# OptronV7_PCB.net
KiCad netlist of a schematic drawn in EAGLE
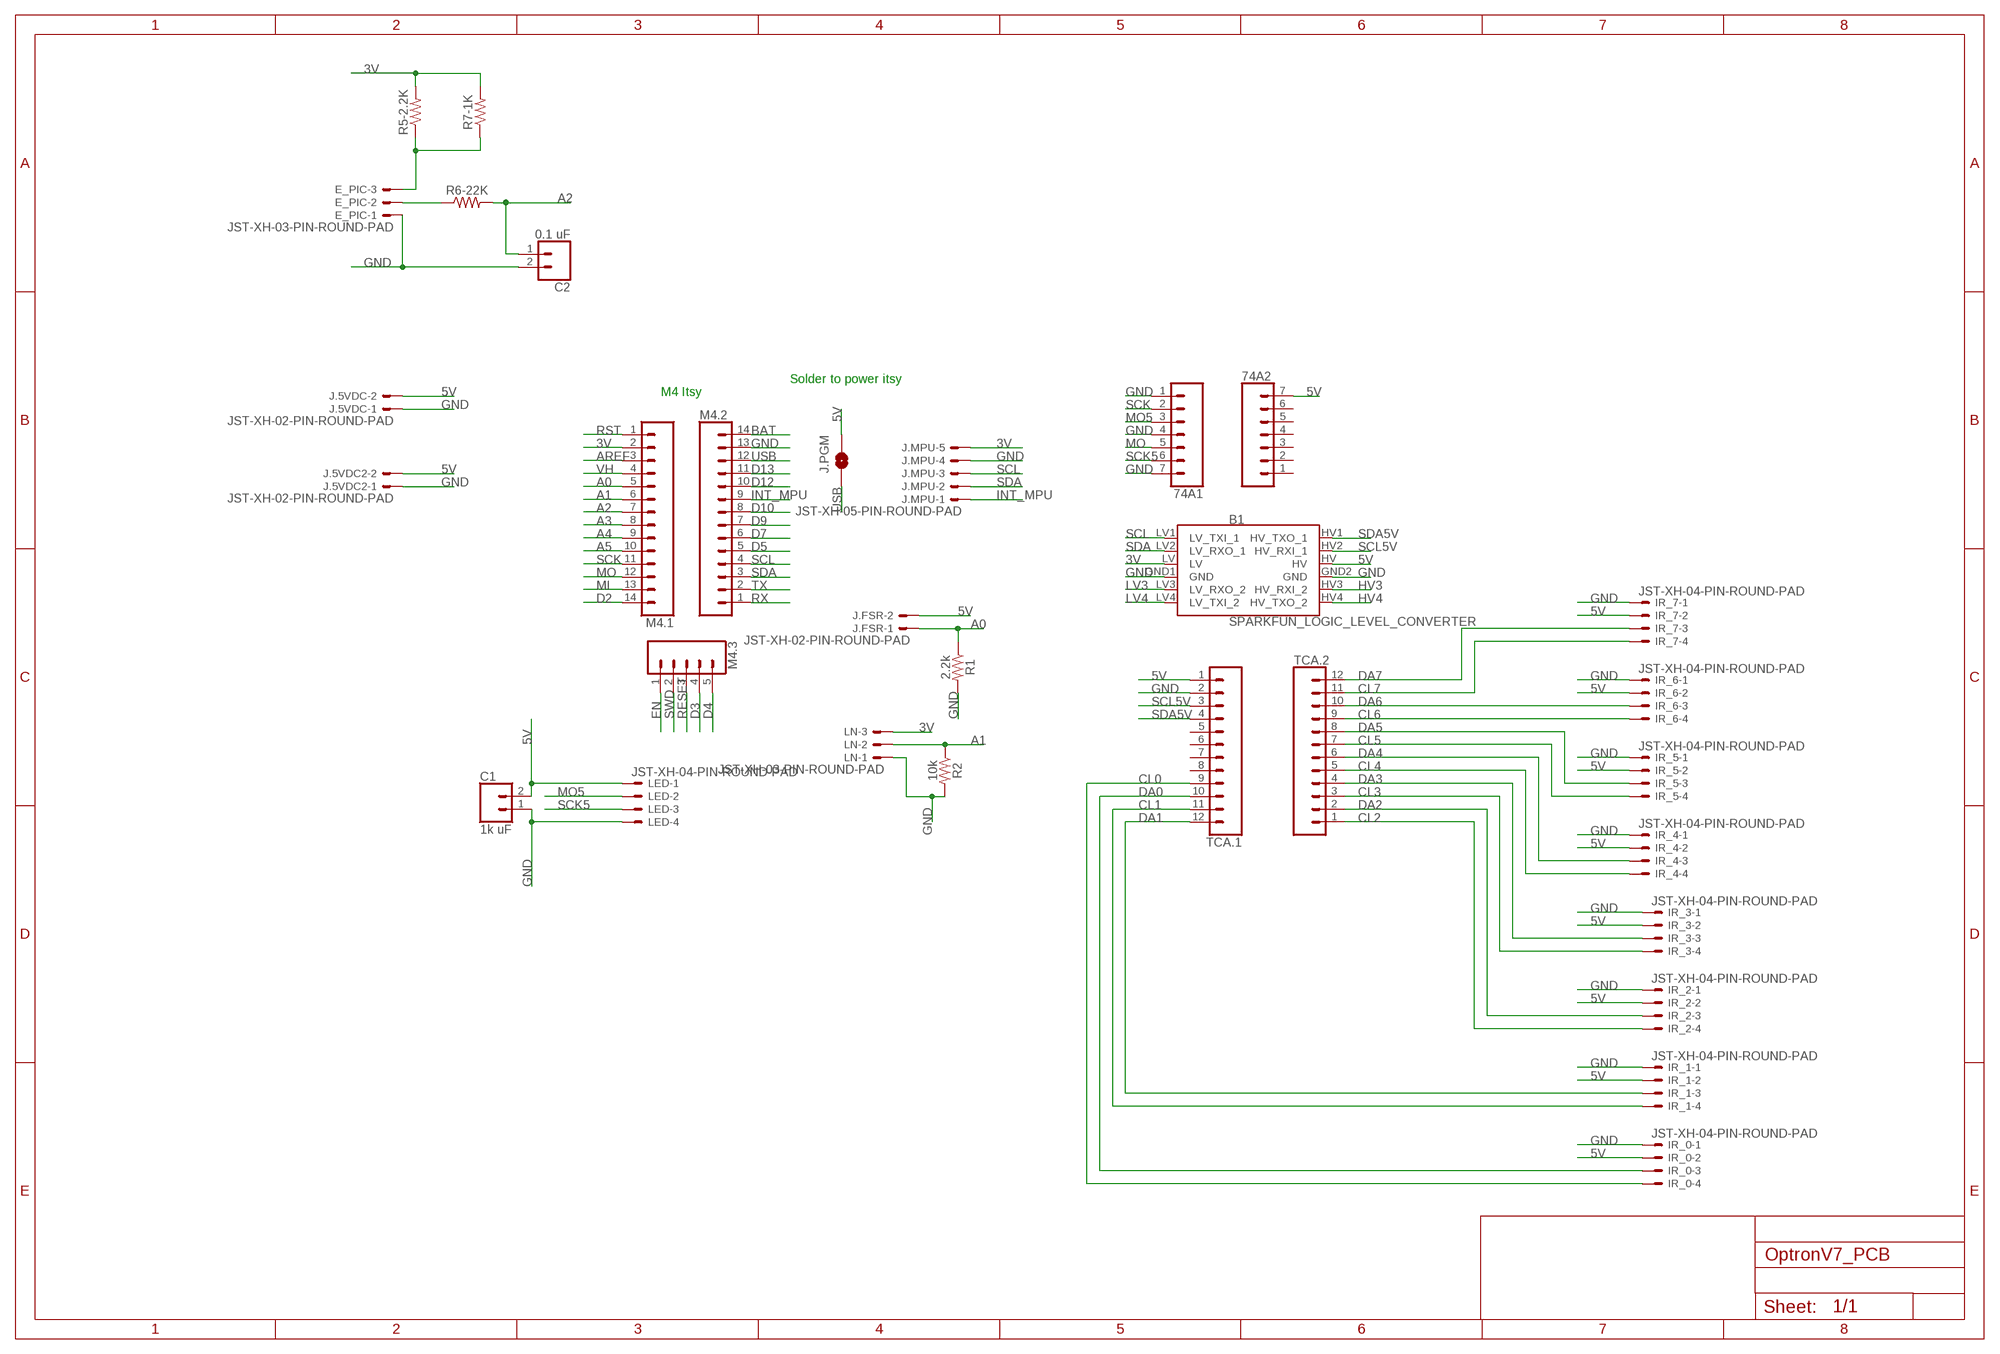
[diagram p0: schematic, sheet 1]

(export (version "E")
  (design (tool "Eeschema 10.0.6"))
  (components
    (comp (ref "74A1")
      (value "CONN_07")
      (footprint "eagle-import:1X07")
      (libsource (lib "eagle-import") (part "CONN_07"))
    )
    (comp (ref "74A2")
      (value "CONN_07")
      (footprint "eagle-import:1X07")
      (libsource (lib "eagle-import") (part "CONN_07"))
    )
    (comp (ref "B1")
      (value "SPARKFUN_LOGIC_LEVEL_CONVERTER")
      (footprint "eagle-import:SPARKFUN_LOGIC_LEVEL_CONVERTER")
      (libsource (lib "eagle-import") (part "SPARKFUN_LOGIC_LEVEL_CONVERTER"))
    )
    (comp (ref "C1")
      (value "1k uF")
      (footprint "eagle-import:1X02")
      (libsource (lib "eagle-import") (part "CONN_02"))
    )
    (comp (ref "C2")
      (value "0.1 uF")
      (footprint "eagle-import:1X02")
      (libsource (lib "eagle-import") (part "CONN_02"))
    )
    (comp (ref "E_PIC")
      (value "JST-XH-03-PIN-ROUND-PAD")
      (footprint "eagle-import:JST-XH-03-PACKAGE-ROUND-PAD")
      (libsource (lib "eagle-import") (part "JST-XH-03-PIN-ROUND-PAD"))
    )
    (comp (ref "IR_0")
      (value "JST-XH-04-PIN-ROUND-PAD")
      (footprint "eagle-import:JST-XH-04-PACKAGE-ROUND-PAD")
      (libsource (lib "eagle-import") (part "JST-XH-04-PIN-ROUND-PAD"))
    )
    (comp (ref "IR_1")
      (value "JST-XH-04-PIN-ROUND-PAD")
      (footprint "eagle-import:JST-XH-04-PACKAGE-ROUND-PAD")
      (libsource (lib "eagle-import") (part "JST-XH-04-PIN-ROUND-PAD"))
    )
    (comp (ref "IR_2")
      (value "JST-XH-04-PIN-ROUND-PAD")
      (footprint "eagle-import:JST-XH-04-PACKAGE-ROUND-PAD")
      (libsource (lib "eagle-import") (part "JST-XH-04-PIN-ROUND-PAD"))
    )
    (comp (ref "IR_3")
      (value "JST-XH-04-PIN-ROUND-PAD")
      (footprint "eagle-import:JST-XH-04-PACKAGE-ROUND-PAD")
      (libsource (lib "eagle-import") (part "JST-XH-04-PIN-ROUND-PAD"))
    )
    (comp (ref "IR_4")
      (value "JST-XH-04-PIN-ROUND-PAD")
      (footprint "eagle-import:JST-XH-04-PACKAGE-ROUND-PAD")
      (libsource (lib "eagle-import") (part "JST-XH-04-PIN-ROUND-PAD"))
    )
    (comp (ref "IR_5")
      (value "JST-XH-04-PIN-ROUND-PAD")
      (footprint "eagle-import:JST-XH-04-PACKAGE-ROUND-PAD")
      (libsource (lib "eagle-import") (part "JST-XH-04-PIN-ROUND-PAD"))
    )
    (comp (ref "IR_6")
      (value "JST-XH-04-PIN-ROUND-PAD")
      (footprint "eagle-import:JST-XH-04-PACKAGE-ROUND-PAD")
      (libsource (lib "eagle-import") (part "JST-XH-04-PIN-ROUND-PAD"))
    )
    (comp (ref "IR_7")
      (value "JST-XH-04-PIN-ROUND-PAD")
      (footprint "eagle-import:JST-XH-04-PACKAGE-ROUND-PAD")
      (libsource (lib "eagle-import") (part "JST-XH-04-PIN-ROUND-PAD"))
    )
    (comp (ref "J.5VDC")
      (value "JST-XH-02-PIN-ROUND-PAD")
      (footprint "eagle-import:JST-XH-02-PACKAGE-ROUND-PAD")
      (libsource (lib "eagle-import") (part "JST-XH-02-PIN-ROUND-PAD"))
    )
    (comp (ref "J.5VDC2")
      (value "JST-XH-02-PIN-ROUND-PAD")
      (footprint "eagle-import:JST-XH-02-PACKAGE-ROUND-PAD")
      (libsource (lib "eagle-import") (part "JST-XH-02-PIN-ROUND-PAD"))
    )
    (comp (ref "J.FSR")
      (value "JST-XH-02-PIN-ROUND-PAD")
      (footprint "eagle-import:JST-XH-02-PACKAGE-ROUND-PAD")
      (libsource (lib "eagle-import") (part "JST-XH-02-PIN-ROUND-PAD"))
    )
    (comp (ref "J.MPU")
      (value "JST-XH-05-PIN-ROUND-PAD")
      (footprint "eagle-import:JST-XH-05-PACKAGE-ROUND-PAD")
      (libsource (lib "eagle-import") (part "JST-XH-05-PIN-ROUND-PAD"))
    )
    (comp (ref "J.PGM")
      (value "JUMPER-SMT_2_NO_NO-SILK")
      (footprint "eagle-import:SMT-JUMPER_2_NO_NO-SILK")
      (libsource (lib "eagle-import") (part "JUMPER-SMT_2_NO_NO-SILK"))
    )
    (comp (ref "LED")
      (value "JST-XH-04-PIN-ROUND-PAD")
      (footprint "eagle-import:JST-XH-04-PACKAGE-ROUND-PAD")
      (libsource (lib "eagle-import") (part "JST-XH-04-PIN-ROUND-PAD"))
    )
    (comp (ref "LN")
      (value "JST-XH-03-PIN-ROUND-PAD")
      (footprint "eagle-import:JST-XH-03-PACKAGE-ROUND-PAD")
      (libsource (lib "eagle-import") (part "JST-XH-03-PIN-ROUND-PAD"))
    )
    (comp (ref "M4.1")
      (value "CONN_14")
      (footprint "eagle-import:1X14")
      (libsource (lib "eagle-import") (part "CONN_14"))
    )
    (comp (ref "M4.2")
      (value "CONN_14")
      (footprint "eagle-import:1X14")
      (libsource (lib "eagle-import") (part "CONN_14"))
    )
    (comp (ref "M4.3")
      (value "CONN_05")
      (footprint "eagle-import:1X05")
      (libsource (lib "eagle-import") (part "CONN_05"))
    )
    (comp (ref "R1")
      (value "2.2k")
      (footprint "eagle-import:AXIAL-0.3")
      (libsource (lib "eagle-import") (part "10KOHM-HORIZ-1/4W-5%"))
    )
    (comp (ref "R2")
      (value "10k")
      (footprint "eagle-import:AXIAL-0.3")
      (libsource (lib "eagle-import") (part "10KOHM-HORIZ-1/4W-5%"))
    )
    (comp (ref "R5-2.2K")
      (value "RESISTORAXIAL-0.3")
      (footprint "eagle-import:AXIAL-0.3")
      (libsource (lib "eagle-import") (part "RESISTORAXIAL-0.3"))
    )
    (comp (ref "R6-22K")
      (value "RESISTORAXIAL-0.3")
      (footprint "eagle-import:AXIAL-0.3")
      (libsource (lib "eagle-import") (part "RESISTORAXIAL-0.3"))
    )
    (comp (ref "R7-1K")
      (value "RESISTORAXIAL-0.3")
      (footprint "eagle-import:AXIAL-0.3")
      (libsource (lib "eagle-import") (part "RESISTORAXIAL-0.3"))
    )
    (comp (ref "TCA.1")
      (value "CONN_12")
      (footprint "eagle-import:1X12")
      (libsource (lib "eagle-import") (part "CONN_12"))
    )
    (comp (ref "TCA.2")
      (value "CONN_12")
      (footprint "eagle-import:1X12")
      (libsource (lib "eagle-import") (part "CONN_12"))
    )
  )
  (nets
    (net (code "1") (name "/3V") (class "Default")
      (node (ref "B1") (pin "LV") (pinfunction "LV_LV") (pintype "power_in"))
      (node (ref "J.MPU") (pin "5") (pinfunction "S_5") (pintype "passive"))
      (node (ref "LN") (pin "3") (pinfunction "S_3") (pintype "passive"))
      (node (ref "M4.1") (pin "2") (pinfunction "2_2") (pintype "passive"))
      (node (ref "R5-2.2K") (pin "P$2") (pinfunction "2_P$2") (pintype "passive"))
      (node (ref "R7-1K") (pin "P$2") (pinfunction "2_P$2") (pintype "passive"))
    )
    (net (code "2") (name "/5V") (class "Default")
      (node (ref "74A2") (pin "7") (pinfunction "7_7") (pintype "passive"))
      (node (ref "B1") (pin "HV") (pinfunction "HV_HV") (pintype "power_in"))
      (node (ref "C1") (pin "2") (pinfunction "2_2") (pintype "passive"))
      (node (ref "IR_0") (pin "2") (pinfunction "S_2") (pintype "passive"))
      (node (ref "IR_1") (pin "2") (pinfunction "S_2") (pintype "passive"))
      (node (ref "IR_2") (pin "2") (pinfunction "S_2") (pintype "passive"))
      (node (ref "IR_3") (pin "2") (pinfunction "S_2") (pintype "passive"))
      (node (ref "IR_4") (pin "2") (pinfunction "S_2") (pintype "passive"))
      (node (ref "IR_5") (pin "2") (pinfunction "S_2") (pintype "passive"))
      (node (ref "IR_6") (pin "2") (pinfunction "S_2") (pintype "passive"))
      (node (ref "IR_7") (pin "2") (pinfunction "S_2") (pintype "passive"))
      (node (ref "J.5VDC") (pin "2") (pinfunction "S_2") (pintype "passive"))
      (node (ref "J.5VDC2") (pin "2") (pinfunction "S_2") (pintype "passive"))
      (node (ref "J.FSR") (pin "2") (pinfunction "S_2") (pintype "passive"))
      (node (ref "J.PGM") (pin "2") (pinfunction "2_2") (pintype "passive"))
      (node (ref "LED") (pin "1") (pinfunction "S_1") (pintype "passive"))
      (node (ref "TCA.1") (pin "1") (pinfunction "1_1") (pintype "passive"))
    )
    (net (code "3") (name "/A0") (class "Default")
      (node (ref "J.FSR") (pin "1") (pinfunction "S_1") (pintype "passive"))
      (node (ref "M4.1") (pin "5") (pinfunction "5_5") (pintype "passive"))
      (node (ref "R1") (pin "P$1") (pinfunction "1_P$1") (pintype "passive"))
    )
    (net (code "4") (name "/A1") (class "Default")
      (node (ref "LN") (pin "2") (pinfunction "S_2") (pintype "passive"))
      (node (ref "M4.1") (pin "6") (pinfunction "6_6") (pintype "passive"))
      (node (ref "R2") (pin "P$1") (pinfunction "1_P$1") (pintype "passive"))
    )
    (net (code "5") (name "/A2") (class "Default")
      (node (ref "C2") (pin "1") (pinfunction "1_1") (pintype "passive"))
      (node (ref "M4.1") (pin "7") (pinfunction "7_7") (pintype "passive"))
      (node (ref "R6-22K") (pin "P$2") (pinfunction "2_P$2") (pintype "passive"))
    )
    (net (code "6") (name "/A3") (class "Default")
      (node (ref "M4.1") (pin "8") (pinfunction "8_8") (pintype "passive"))
    )
    (net (code "7") (name "/A4") (class "Default")
      (node (ref "M4.1") (pin "9") (pinfunction "9_9") (pintype "passive"))
    )
    (net (code "8") (name "/A5") (class "Default")
      (node (ref "M4.1") (pin "10") (pinfunction "10_10") (pintype "passive"))
    )
    (net (code "9") (name "/AREF") (class "Default")
      (node (ref "M4.1") (pin "3") (pinfunction "3_3") (pintype "passive"))
    )
    (net (code "10") (name "/BAT") (class "Default")
      (node (ref "M4.2") (pin "14") (pinfunction "14_14") (pintype "passive"))
    )
    (net (code "11") (name "/CL0") (class "Default")
      (node (ref "IR_0") (pin "4") (pinfunction "S_4") (pintype "passive"))
      (node (ref "TCA.1") (pin "9") (pinfunction "9_9") (pintype "passive"))
    )
    (net (code "12") (name "/CL1") (class "Default")
      (node (ref "IR_1") (pin "4") (pinfunction "S_4") (pintype "passive"))
      (node (ref "TCA.1") (pin "11") (pinfunction "11_11") (pintype "passive"))
    )
    (net (code "13") (name "/CL2") (class "Default")
      (node (ref "IR_2") (pin "4") (pinfunction "S_4") (pintype "passive"))
      (node (ref "TCA.2") (pin "1") (pinfunction "1_1") (pintype "passive"))
    )
    (net (code "14") (name "/CL3") (class "Default")
      (node (ref "IR_3") (pin "4") (pinfunction "S_4") (pintype "passive"))
      (node (ref "TCA.2") (pin "3") (pinfunction "3_3") (pintype "passive"))
    )
    (net (code "15") (name "/CL4") (class "Default")
      (node (ref "IR_4") (pin "4") (pinfunction "S_4") (pintype "passive"))
      (node (ref "TCA.2") (pin "5") (pinfunction "5_5") (pintype "passive"))
    )
    (net (code "16") (name "/CL5") (class "Default")
      (node (ref "IR_5") (pin "4") (pinfunction "S_4") (pintype "passive"))
      (node (ref "TCA.2") (pin "7") (pinfunction "7_7") (pintype "passive"))
    )
    (net (code "17") (name "/CL6") (class "Default")
      (node (ref "IR_6") (pin "4") (pinfunction "S_4") (pintype "passive"))
      (node (ref "TCA.2") (pin "9") (pinfunction "9_9") (pintype "passive"))
    )
    (net (code "18") (name "/CL7") (class "Default")
      (node (ref "IR_7") (pin "4") (pinfunction "S_4") (pintype "passive"))
      (node (ref "TCA.2") (pin "11") (pinfunction "11_11") (pintype "passive"))
    )
    (net (code "19") (name "/D2") (class "Default")
      (node (ref "M4.1") (pin "14") (pinfunction "14_14") (pintype "passive"))
    )
    (net (code "20") (name "/D3") (class "Default")
      (node (ref "M4.3") (pin "4") (pinfunction "4_4") (pintype "passive"))
    )
    (net (code "21") (name "/D4") (class "Default")
      (node (ref "M4.3") (pin "5") (pinfunction "5_5") (pintype "passive"))
    )
    (net (code "22") (name "/D5") (class "Default")
      (node (ref "M4.2") (pin "5") (pinfunction "5_5") (pintype "passive"))
    )
    (net (code "23") (name "/D7") (class "Default")
      (node (ref "M4.2") (pin "6") (pinfunction "6_6") (pintype "passive"))
    )
    (net (code "24") (name "/D9") (class "Default")
      (node (ref "M4.2") (pin "7") (pinfunction "7_7") (pintype "passive"))
    )
    (net (code "25") (name "/D10") (class "Default")
      (node (ref "M4.2") (pin "8") (pinfunction "8_8") (pintype "passive"))
    )
    (net (code "26") (name "/D12") (class "Default")
      (node (ref "M4.2") (pin "10") (pinfunction "10_10") (pintype "passive"))
    )
    (net (code "27") (name "/D13") (class "Default")
      (node (ref "M4.2") (pin "11") (pinfunction "11_11") (pintype "passive"))
    )
    (net (code "28") (name "/DA0") (class "Default")
      (node (ref "IR_0") (pin "3") (pinfunction "S_3") (pintype "passive"))
      (node (ref "TCA.1") (pin "10") (pinfunction "10_10") (pintype "passive"))
    )
    (net (code "29") (name "/DA1") (class "Default")
      (node (ref "IR_1") (pin "3") (pinfunction "S_3") (pintype "passive"))
      (node (ref "TCA.1") (pin "12") (pinfunction "12_12") (pintype "passive"))
    )
    (net (code "30") (name "/DA2") (class "Default")
      (node (ref "IR_2") (pin "3") (pinfunction "S_3") (pintype "passive"))
      (node (ref "TCA.2") (pin "2") (pinfunction "2_2") (pintype "passive"))
    )
    (net (code "31") (name "/DA3") (class "Default")
      (node (ref "IR_3") (pin "3") (pinfunction "S_3") (pintype "passive"))
      (node (ref "TCA.2") (pin "4") (pinfunction "4_4") (pintype "passive"))
    )
    (net (code "32") (name "/DA4") (class "Default")
      (node (ref "IR_4") (pin "3") (pinfunction "S_3") (pintype "passive"))
      (node (ref "TCA.2") (pin "6") (pinfunction "6_6") (pintype "passive"))
    )
    (net (code "33") (name "/DA5") (class "Default")
      (node (ref "IR_5") (pin "3") (pinfunction "S_3") (pintype "passive"))
      (node (ref "TCA.2") (pin "8") (pinfunction "8_8") (pintype "passive"))
    )
    (net (code "34") (name "/DA6") (class "Default")
      (node (ref "IR_6") (pin "3") (pinfunction "S_3") (pintype "passive"))
      (node (ref "TCA.2") (pin "10") (pinfunction "10_10") (pintype "passive"))
    )
    (net (code "35") (name "/DA7") (class "Default")
      (node (ref "IR_7") (pin "3") (pinfunction "S_3") (pintype "passive"))
      (node (ref "TCA.2") (pin "12") (pinfunction "12_12") (pintype "passive"))
    )
    (net (code "36") (name "/EN") (class "Default")
      (node (ref "M4.3") (pin "1") (pinfunction "1_1") (pintype "passive"))
    )
    (net (code "37") (name "/GND") (class "Default")
      (node (ref "74A1") (pin "1") (pinfunction "1_1") (pintype "passive"))
      (node (ref "74A1") (pin "4") (pinfunction "4_4") (pintype "passive"))
      (node (ref "74A1") (pin "7") (pinfunction "7_7") (pintype "passive"))
      (node (ref "B1") (pin "GND1") (pinfunction "GND_GND1") (pintype "power_in"))
      (node (ref "B1") (pin "GND2") (pinfunction "GND_GND2") (pintype "power_in"))
      (node (ref "C1") (pin "1") (pinfunction "1_1") (pintype "passive"))
      (node (ref "C2") (pin "2") (pinfunction "2_2") (pintype "passive"))
      (node (ref "E_PIC") (pin "1") (pinfunction "S_1") (pintype "passive"))
      (node (ref "IR_0") (pin "1") (pinfunction "S_1") (pintype "passive"))
      (node (ref "IR_1") (pin "1") (pinfunction "S_1") (pintype "passive"))
      (node (ref "IR_2") (pin "1") (pinfunction "S_1") (pintype "passive"))
      (node (ref "IR_3") (pin "1") (pinfunction "S_1") (pintype "passive"))
      (node (ref "IR_4") (pin "1") (pinfunction "S_1") (pintype "passive"))
      (node (ref "IR_5") (pin "1") (pinfunction "S_1") (pintype "passive"))
      (node (ref "IR_6") (pin "1") (pinfunction "S_1") (pintype "passive"))
      (node (ref "IR_7") (pin "1") (pinfunction "S_1") (pintype "passive"))
      (node (ref "J.5VDC") (pin "1") (pinfunction "S_1") (pintype "passive"))
      (node (ref "J.5VDC2") (pin "1") (pinfunction "S_1") (pintype "passive"))
      (node (ref "J.MPU") (pin "4") (pinfunction "S_4") (pintype "passive"))
      (node (ref "LED") (pin "4") (pinfunction "S_4") (pintype "passive"))
      (node (ref "LN") (pin "1") (pinfunction "S_1") (pintype "passive"))
      (node (ref "M4.2") (pin "13") (pinfunction "13_13") (pintype "passive"))
      (node (ref "R1") (pin "P$2") (pinfunction "2_P$2") (pintype "passive"))
      (node (ref "R2") (pin "P$2") (pinfunction "2_P$2") (pintype "passive"))
      (node (ref "TCA.1") (pin "2") (pinfunction "2_2") (pintype "passive"))
    )
    (net (code "38") (name "/HV3") (class "Default")
      (node (ref "B1") (pin "HV3") (pinfunction "HV_RXI_2_HV3") (pintype "bidirectional"))
    )
    (net (code "39") (name "/HV4") (class "Default")
      (node (ref "B1") (pin "HV4") (pinfunction "HV_TXO_2_HV4") (pintype "bidirectional"))
    )
    (net (code "40") (name "/INT_MPU") (class "Default")
      (node (ref "J.MPU") (pin "1") (pinfunction "S_1") (pintype "passive"))
      (node (ref "M4.2") (pin "9") (pinfunction "9_9") (pintype "passive"))
    )
    (net (code "41") (name "/LV3") (class "Default")
      (node (ref "B1") (pin "LV3") (pinfunction "LV_RXO_2_LV3") (pintype "bidirectional"))
    )
    (net (code "42") (name "/LV4") (class "Default")
      (node (ref "B1") (pin "LV4") (pinfunction "LV_TXI_2_LV4") (pintype "bidirectional"))
    )
    (net (code "43") (name "/MI") (class "Default")
      (node (ref "M4.1") (pin "13") (pinfunction "13_13") (pintype "passive"))
    )
    (net (code "44") (name "/MO") (class "Default")
      (node (ref "74A1") (pin "5") (pinfunction "5_5") (pintype "passive"))
      (node (ref "M4.1") (pin "12") (pinfunction "12_12") (pintype "passive"))
    )
    (net (code "45") (name "/MO5") (class "Default")
      (node (ref "74A1") (pin "3") (pinfunction "3_3") (pintype "passive"))
      (node (ref "LED") (pin "2") (pinfunction "S_2") (pintype "passive"))
    )
    (net (code "46") (name "/RESET") (class "Default")
      (node (ref "M4.3") (pin "3") (pinfunction "3_3") (pintype "passive"))
    )
    (net (code "47") (name "/RST") (class "Default")
      (node (ref "M4.1") (pin "1") (pinfunction "1_1") (pintype "passive"))
    )
    (net (code "48") (name "/RX") (class "Default")
      (node (ref "M4.2") (pin "1") (pinfunction "1_1") (pintype "passive"))
    )
    (net (code "49") (name "/SCK") (class "Default")
      (node (ref "74A1") (pin "2") (pinfunction "2_2") (pintype "passive"))
      (node (ref "M4.1") (pin "11") (pinfunction "11_11") (pintype "passive"))
    )
    (net (code "50") (name "/SCK5") (class "Default")
      (node (ref "74A1") (pin "6") (pinfunction "6_6") (pintype "passive"))
      (node (ref "LED") (pin "3") (pinfunction "S_3") (pintype "passive"))
    )
    (net (code "51") (name "/SCL") (class "Default")
      (node (ref "B1") (pin "LV1") (pinfunction "LV_TXI_1_LV1") (pintype "bidirectional"))
      (node (ref "J.MPU") (pin "3") (pinfunction "S_3") (pintype "passive"))
      (node (ref "M4.2") (pin "4") (pinfunction "4_4") (pintype "passive"))
    )
    (net (code "52") (name "/SCL5V") (class "Default")
      (node (ref "B1") (pin "HV2") (pinfunction "HV_RXI_1_HV2") (pintype "bidirectional"))
      (node (ref "TCA.1") (pin "3") (pinfunction "3_3") (pintype "passive"))
    )
    (net (code "53") (name "/SDA") (class "Default")
      (node (ref "B1") (pin "LV2") (pinfunction "LV_RXO_1_LV2") (pintype "bidirectional"))
      (node (ref "J.MPU") (pin "2") (pinfunction "S_2") (pintype "passive"))
      (node (ref "M4.2") (pin "3") (pinfunction "3_3") (pintype "passive"))
    )
    (net (code "54") (name "/SDA5V") (class "Default")
      (node (ref "B1") (pin "HV1") (pinfunction "HV_TXO_1_HV1") (pintype "bidirectional"))
      (node (ref "TCA.1") (pin "4") (pinfunction "4_4") (pintype "passive"))
    )
    (net (code "55") (name "/SWD") (class "Default")
      (node (ref "M4.3") (pin "2") (pinfunction "2_2") (pintype "passive"))
    )
    (net (code "56") (name "/TX") (class "Default")
      (node (ref "M4.2") (pin "2") (pinfunction "2_2") (pintype "passive"))
    )
    (net (code "57") (name "/USB") (class "Default")
      (node (ref "J.PGM") (pin "1") (pinfunction "1_1") (pintype "passive"))
      (node (ref "M4.2") (pin "12") (pinfunction "12_12") (pintype "passive"))
    )
    (net (code "58") (name "/VH") (class "Default")
      (node (ref "M4.1") (pin "4") (pinfunction "4_4") (pintype "passive"))
    )
    (net (code "59") (name "Net-(E_PICB-S)") (class "Default")
      (node (ref "E_PIC") (pin "2") (pinfunction "S_2") (pintype "passive"))
      (node (ref "R6-22K") (pin "P$1") (pinfunction "1_P$1") (pintype "passive"))
    )
    (net (code "60") (name "Net-(E_PICC-S)") (class "Default")
      (node (ref "E_PIC") (pin "3") (pinfunction "S_3") (pintype "passive"))
      (node (ref "R5-2.2K") (pin "P$1") (pinfunction "1_P$1") (pintype "passive"))
      (node (ref "R7-1K") (pin "P$1") (pinfunction "1_P$1") (pintype "passive"))
    )
    (net (code "61") (name "unconnected-(74A2-Pad1)") (class "Default")
      (node (ref "74A2") (pin "1") (pinfunction "1_1") (pintype "passive"))
    )
    (net (code "62") (name "unconnected-(74A2-Pad2)") (class "Default")
      (node (ref "74A2") (pin "2") (pinfunction "2_2") (pintype "passive"))
    )
    (net (code "63") (name "unconnected-(74A2-Pad3)") (class "Default")
      (node (ref "74A2") (pin "3") (pinfunction "3_3") (pintype "passive"))
    )
    (net (code "64") (name "unconnected-(74A2-Pad4)") (class "Default")
      (node (ref "74A2") (pin "4") (pinfunction "4_4") (pintype "passive"))
    )
    (net (code "65") (name "unconnected-(74A2-Pad5)") (class "Default")
      (node (ref "74A2") (pin "5") (pinfunction "5_5") (pintype "passive"))
    )
    (net (code "66") (name "unconnected-(74A2-Pad6)") (class "Default")
      (node (ref "74A2") (pin "6") (pinfunction "6_6") (pintype "passive"))
    )
    (net (code "67") (name "unconnected-(TCA.1-Pad5)") (class "Default")
      (node (ref "TCA.1") (pin "5") (pinfunction "5_5") (pintype "passive"))
    )
    (net (code "68") (name "unconnected-(TCA.1-Pad6)") (class "Default")
      (node (ref "TCA.1") (pin "6") (pinfunction "6_6") (pintype "passive"))
    )
    (net (code "69") (name "unconnected-(TCA.1-Pad7)") (class "Default")
      (node (ref "TCA.1") (pin "7") (pinfunction "7_7") (pintype "passive"))
    )
    (net (code "70") (name "unconnected-(TCA.1-Pad8)") (class "Default")
      (node (ref "TCA.1") (pin "8") (pinfunction "8_8") (pintype "passive"))
    )
  )
)
